# main.net
KiCad netlist of a schematic drawn in EAGLE
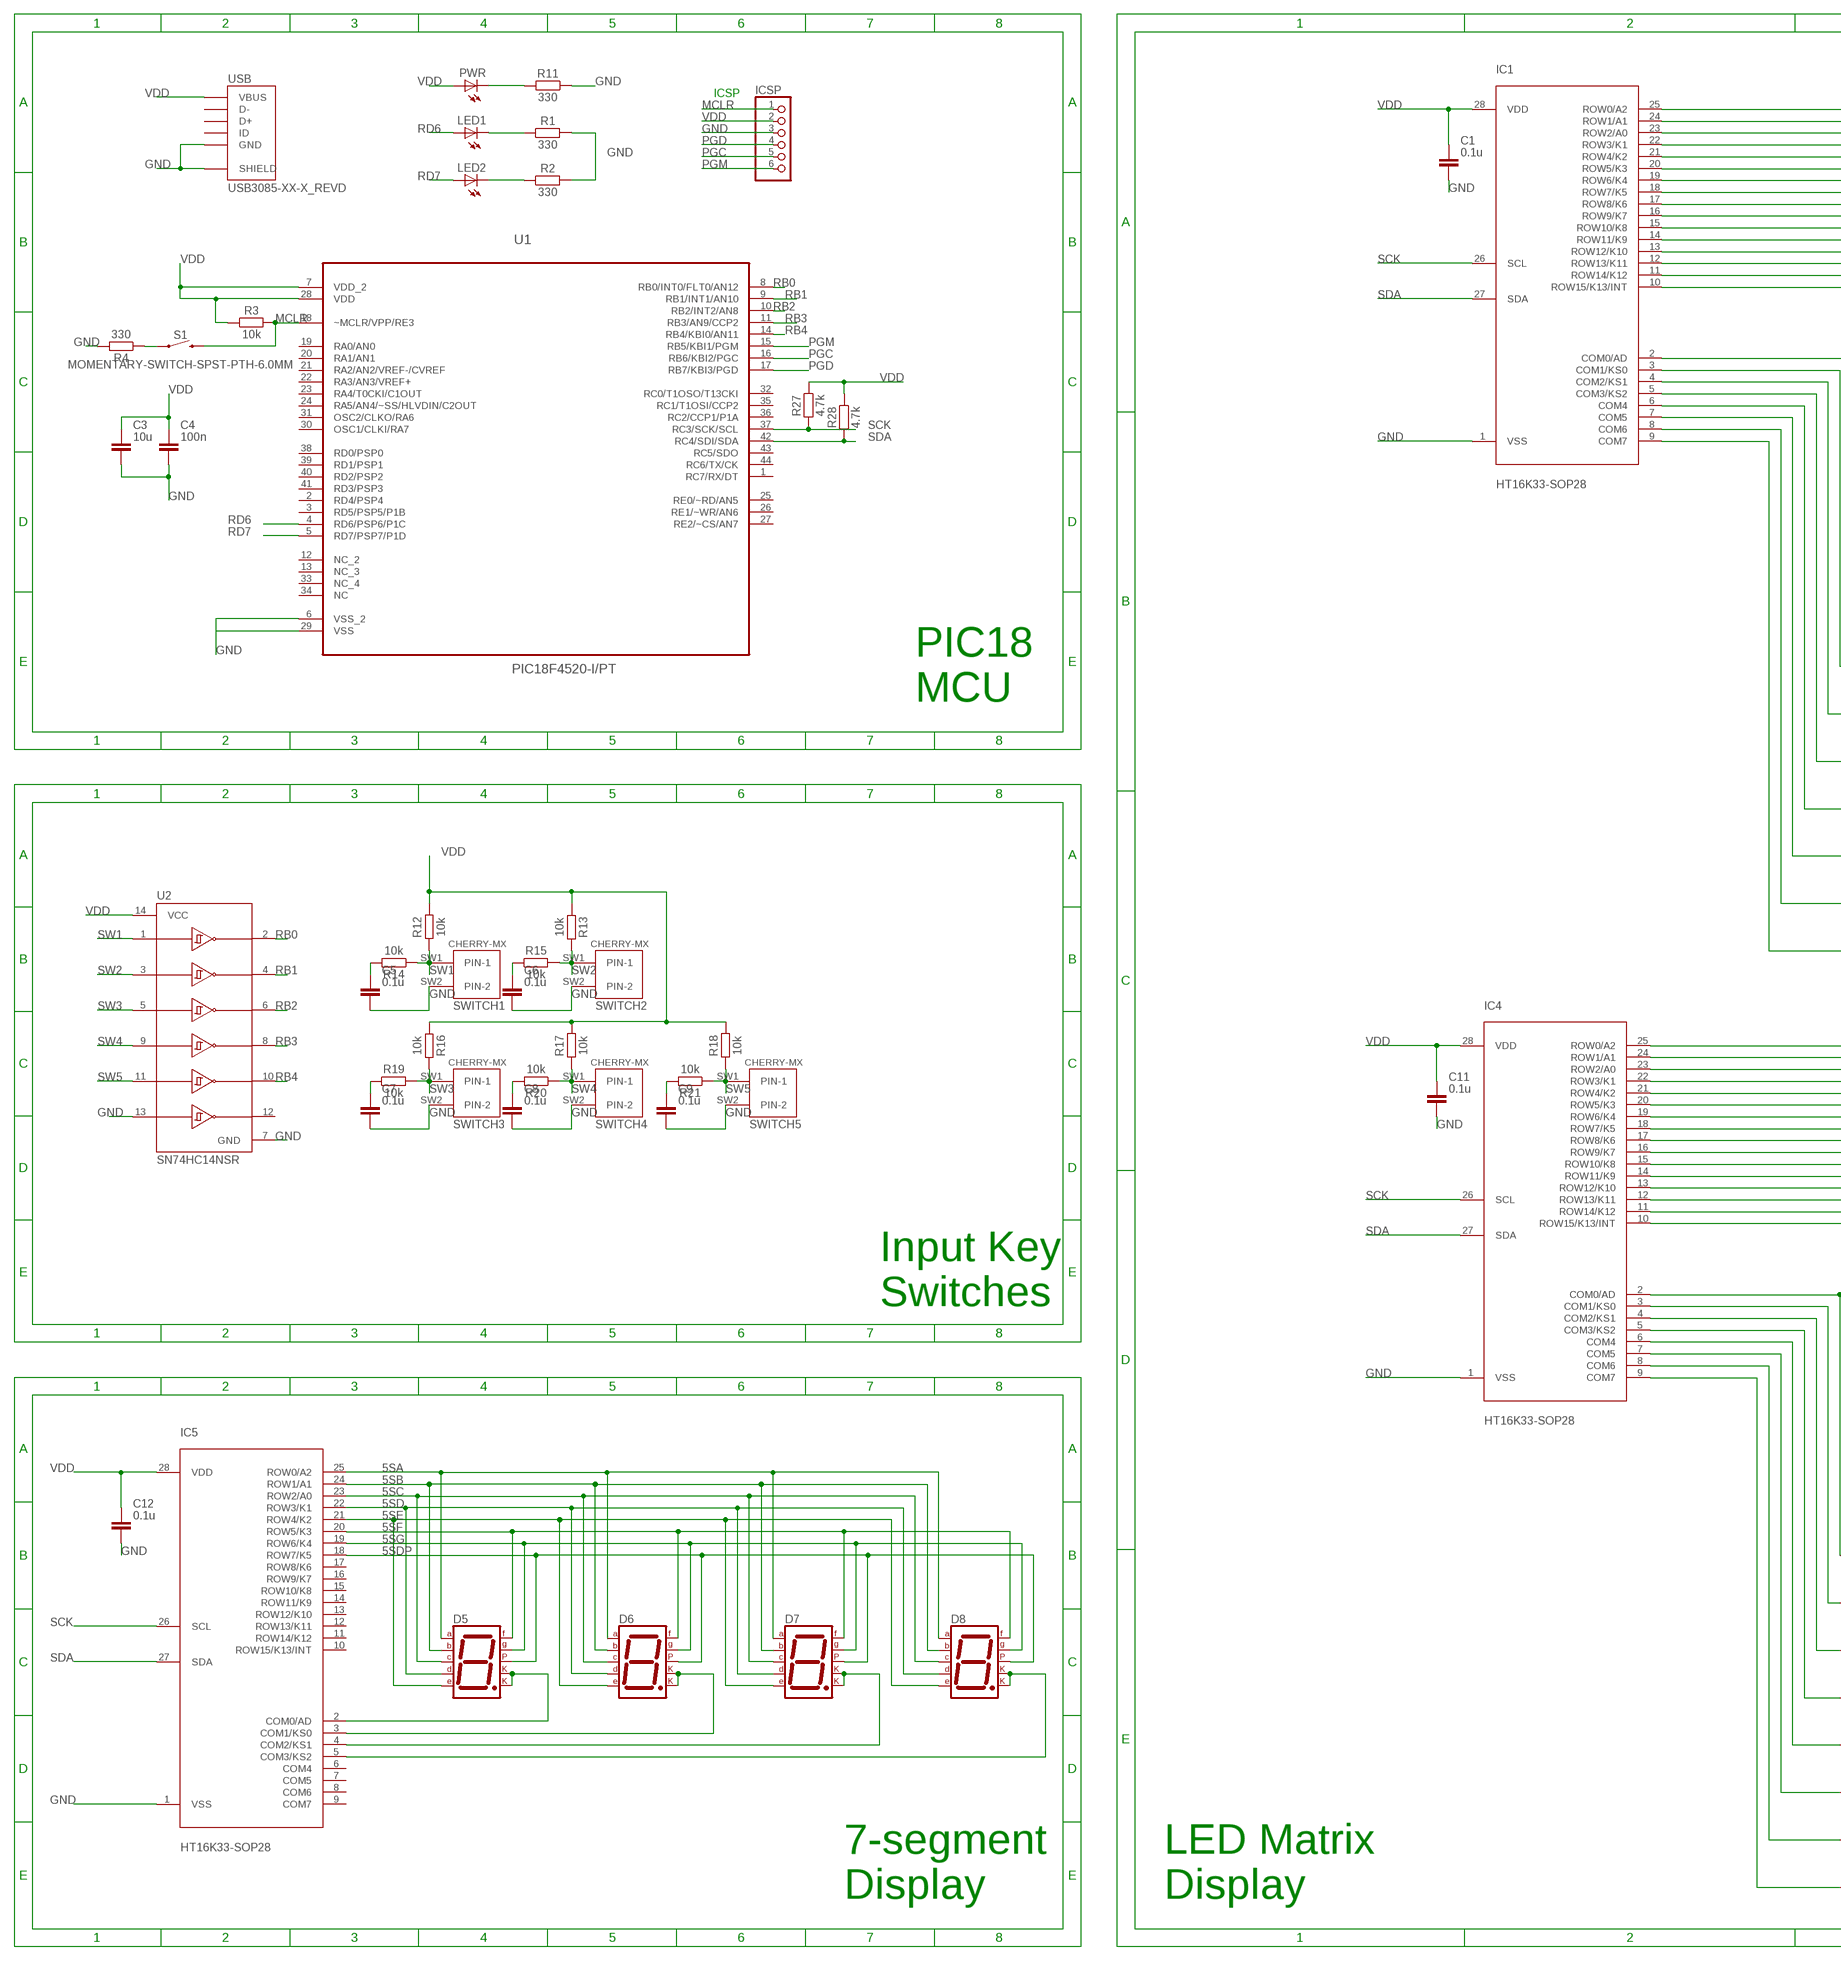
[diagram p0: schematic, sheet 1, part 1 of 2]
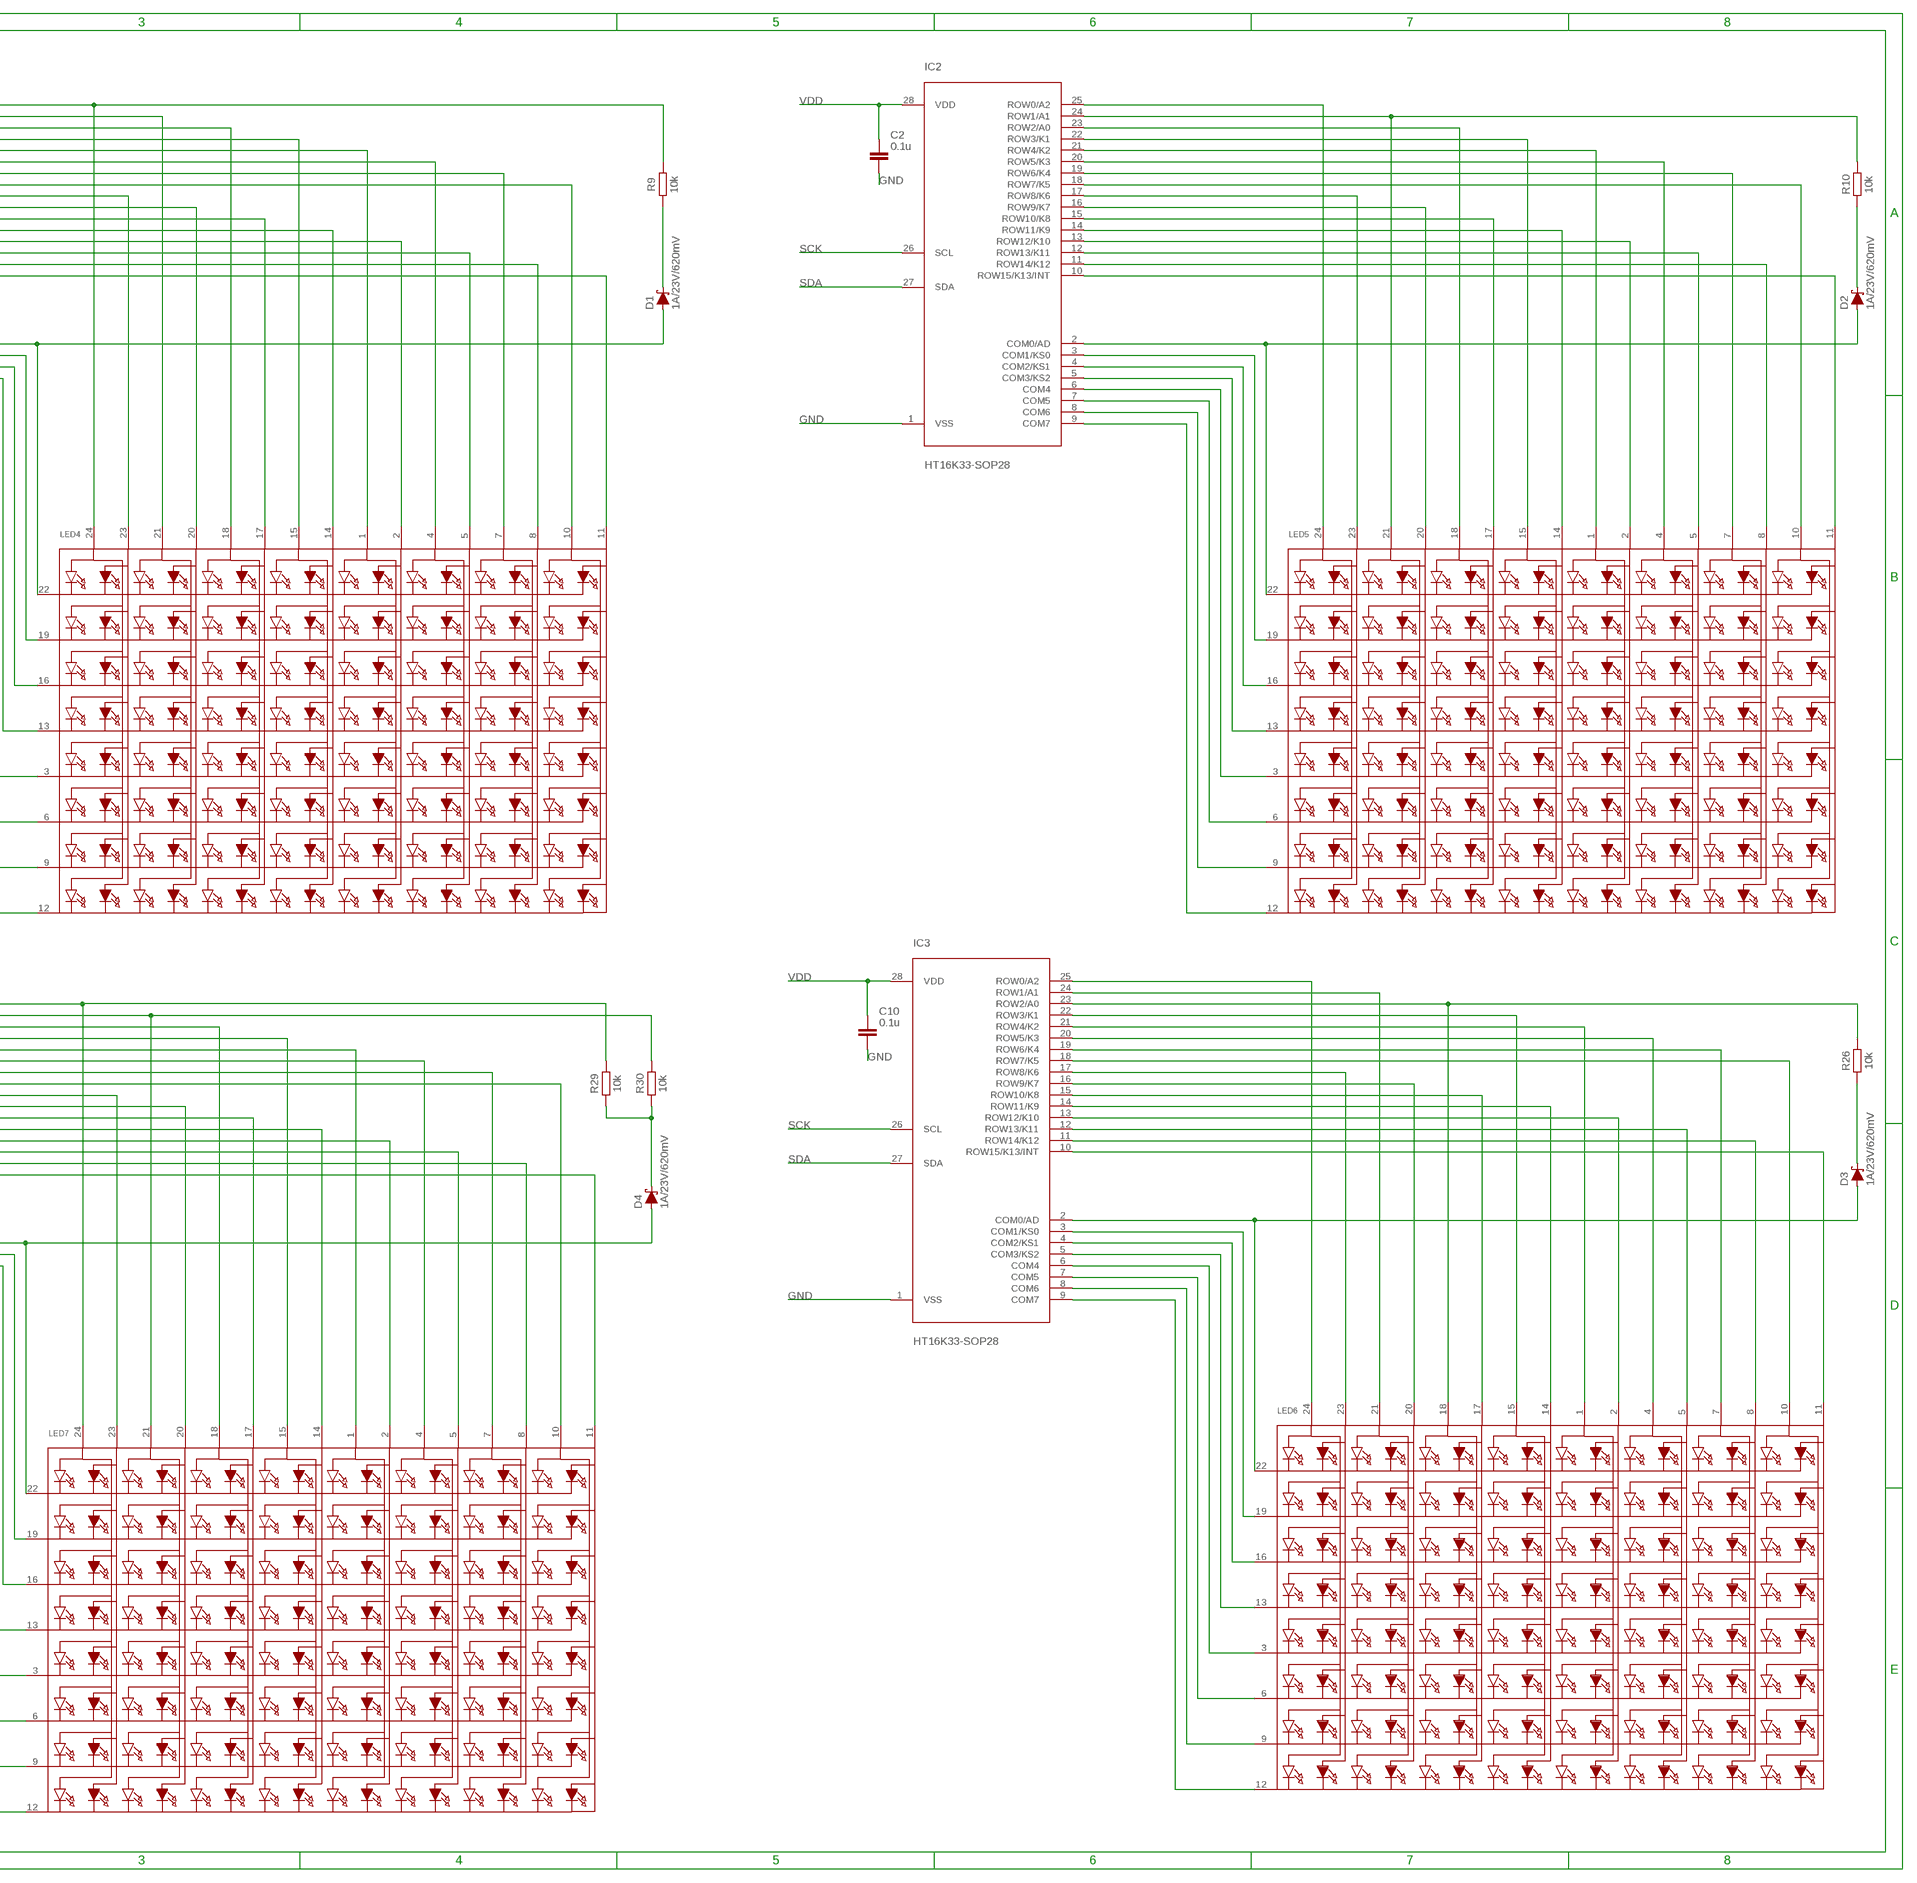
[diagram p1: schematic, sheet 1, part 2 of 2]

(export (version "E")
  (design (tool "Eeschema 10.0.6"))
  (components
    (comp (ref "C1")
      (value "0.1u")
      (footprint "eagle-import:CAPC2012X110")
      (libsource (lib "eagle-import") (part "CCHIP-0805(2012-METRIC)_"))
    )
    (comp (ref "C2")
      (value "0.1u")
      (footprint "eagle-import:CAPC2012X110")
      (libsource (lib "eagle-import") (part "CCHIP-0805(2012-METRIC)_"))
    )
    (comp (ref "C3")
      (value "10u")
      (footprint "eagle-import:CAPC2012X110")
      (libsource (lib "eagle-import") (part "CCHIP-0805(2012-METRIC)_"))
    )
    (comp (ref "C4")
      (value "100n")
      (footprint "eagle-import:CAPC2012X110")
      (libsource (lib "eagle-import") (part "CCHIP-0805(2012-METRIC)_"))
    )
    (comp (ref "C5")
      (value "0.1u")
      (footprint "eagle-import:CAPC2012X110")
      (libsource (lib "eagle-import") (part "CCHIP-0805(2012-METRIC)_"))
    )
    (comp (ref "C6")
      (value "0.1u")
      (footprint "eagle-import:CAPC2012X110")
      (libsource (lib "eagle-import") (part "CCHIP-0805(2012-METRIC)_"))
    )
    (comp (ref "C7")
      (value "0.1u")
      (footprint "eagle-import:CAPC2012X110")
      (libsource (lib "eagle-import") (part "CCHIP-0805(2012-METRIC)_"))
    )
    (comp (ref "C8")
      (value "0.1u")
      (footprint "eagle-import:CAPC2012X110")
      (libsource (lib "eagle-import") (part "CCHIP-0805(2012-METRIC)_"))
    )
    (comp (ref "C9")
      (value "0.1u")
      (footprint "eagle-import:CAPC2012X110")
      (libsource (lib "eagle-import") (part "CCHIP-0805(2012-METRIC)_"))
    )
    (comp (ref "C10")
      (value "0.1u")
      (footprint "eagle-import:CAPC2012X110")
      (libsource (lib "eagle-import") (part "CCHIP-0805(2012-METRIC)_"))
    )
    (comp (ref "C11")
      (value "0.1u")
      (footprint "eagle-import:CAPC2012X110")
      (libsource (lib "eagle-import") (part "CCHIP-0805(2012-METRIC)_"))
    )
    (comp (ref "C12")
      (value "0.1u")
      (footprint "eagle-import:CAPC2012X110")
      (libsource (lib "eagle-import") (part "CCHIP-0805(2012-METRIC)_"))
    )
    (comp (ref "D1")
      (value "1A/23V/620mV")
      (footprint "eagle-import:SOD-323")
      (libsource (lib "eagle-import") (part "DIODE-SCHOTTKY-BAT20J"))
    )
    (comp (ref "D2")
      (value "1A/23V/620mV")
      (footprint "eagle-import:SOD-323")
      (libsource (lib "eagle-import") (part "DIODE-SCHOTTKY-BAT20J"))
    )
    (comp (ref "D3")
      (value "1A/23V/620mV")
      (footprint "eagle-import:SOD-323")
      (libsource (lib "eagle-import") (part "DIODE-SCHOTTKY-BAT20J"))
    )
    (comp (ref "D4")
      (value "1A/23V/620mV")
      (footprint "eagle-import:SOD-323")
      (libsource (lib "eagle-import") (part "DIODE-SCHOTTKY-BAT20J"))
    )
    (comp (ref "D5")
      (value "7SEG-CK")
      (footprint "eagle-import:7SEG-13")
      (libsource (lib "eagle-import") (part "7SEG-CK"))
    )
    (comp (ref "D6")
      (value "7SEG-CK")
      (footprint "eagle-import:7SEG-13")
      (libsource (lib "eagle-import") (part "7SEG-CK"))
    )
    (comp (ref "D7")
      (value "7SEG-CK")
      (footprint "eagle-import:7SEG-13")
      (libsource (lib "eagle-import") (part "7SEG-CK"))
    )
    (comp (ref "D8")
      (value "7SEG-CK")
      (footprint "eagle-import:7SEG-13")
      (libsource (lib "eagle-import") (part "7SEG-CK"))
    )
    (comp (ref "IC1")
      (value "HT16K33-SOP28")
      (footprint "eagle-import:SOIC127P1031X264-28N")
      (libsource (lib "eagle-import") (part "HT16K33-SOP28"))
    )
    (comp (ref "IC2")
      (value "HT16K33-SOP28")
      (footprint "eagle-import:SOIC127P1031X264-28N")
      (libsource (lib "eagle-import") (part "HT16K33-SOP28"))
    )
    (comp (ref "IC3")
      (value "HT16K33-SOP28")
      (footprint "eagle-import:SOIC127P1031X264-28N")
      (libsource (lib "eagle-import") (part "HT16K33-SOP28"))
    )
    (comp (ref "IC4")
      (value "HT16K33-SOP28")
      (footprint "eagle-import:SOIC127P1031X264-28N")
      (libsource (lib "eagle-import") (part "HT16K33-SOP28"))
    )
    (comp (ref "IC5")
      (value "HT16K33-SOP28")
      (footprint "eagle-import:SOIC127P1031X264-28N")
      (libsource (lib "eagle-import") (part "HT16K33-SOP28"))
    )
    (comp (ref "ICSP")
      (value "PINHD-1X6")
      (footprint "eagle-import:1X06")
      (libsource (lib "eagle-import") (part "PINHD-1X6"))
    )
    (comp (ref "LED1")
      (value "LEDCHIPLED_0805")
      (footprint "eagle-import:CHIPLED_0805")
      (libsource (lib "eagle-import") (part "LEDCHIPLED_0805"))
    )
    (comp (ref "LED2")
      (value "LEDCHIPLED_0805")
      (footprint "eagle-import:CHIPLED_0805")
      (libsource (lib "eagle-import") (part "LEDCHIPLED_0805"))
    )
    (comp (ref "LED4")
      (value "SEGMENT_8X8_BICOLOR_ROWCATHODEMI2A883XX")
      (footprint "eagle-import:SEGMENT_BICOL_BL-M12A883XX")
      (libsource (lib "eagle-import") (part "SEGMENT_8X8_BICOLOR_ROWCATHODEMI2A883XX"))
    )
    (comp (ref "LED5")
      (value "SEGMENT_8X8_BICOLOR_ROWCATHODEMI2A883XX")
      (footprint "eagle-import:SEGMENT_BICOL_BL-M12A883XX")
      (libsource (lib "eagle-import") (part "SEGMENT_8X8_BICOLOR_ROWCATHODEMI2A883XX"))
    )
    (comp (ref "LED6")
      (value "SEGMENT_8X8_BICOLOR_ROWCATHODEMI2A883XX")
      (footprint "eagle-import:SEGMENT_BICOL_BL-M12A883XX")
      (libsource (lib "eagle-import") (part "SEGMENT_8X8_BICOLOR_ROWCATHODEMI2A883XX"))
    )
    (comp (ref "LED7")
      (value "SEGMENT_8X8_BICOLOR_ROWCATHODEMI2A883XX")
      (footprint "eagle-import:SEGMENT_BICOL_BL-M12A883XX")
      (libsource (lib "eagle-import") (part "SEGMENT_8X8_BICOLOR_ROWCATHODEMI2A883XX"))
    )
    (comp (ref "PWR")
      (value "LEDCHIPLED_0805")
      (footprint "eagle-import:CHIPLED_0805")
      (libsource (lib "eagle-import") (part "LEDCHIPLED_0805"))
    )
    (comp (ref "R1")
      (value "330")
      (footprint "eagle-import:RESC2012X65")
      (libsource (lib "eagle-import") (part "RCHIP-0805(2012-METRIC)_"))
    )
    (comp (ref "R2")
      (value "330")
      (footprint "eagle-import:RESC2012X65")
      (libsource (lib "eagle-import") (part "RCHIP-0805(2012-METRIC)_"))
    )
    (comp (ref "R3")
      (value "10k")
      (footprint "eagle-import:RESC2012X65")
      (libsource (lib "eagle-import") (part "RCHIP-0805(2012-METRIC)_"))
    )
    (comp (ref "R4")
      (value "330")
      (footprint "eagle-import:RESC2012X65")
      (libsource (lib "eagle-import") (part "RCHIP-0805(2012-METRIC)_"))
    )
    (comp (ref "R9")
      (value "10k")
      (footprint "eagle-import:RESC2012X65")
      (libsource (lib "eagle-import") (part "RCHIP-0805(2012-METRIC)_"))
    )
    (comp (ref "R10")
      (value "10k")
      (footprint "eagle-import:RESC2012X65")
      (libsource (lib "eagle-import") (part "RCHIP-0805(2012-METRIC)_"))
    )
    (comp (ref "R11")
      (value "330")
      (footprint "eagle-import:RESC2012X65")
      (libsource (lib "eagle-import") (part "RCHIP-0805(2012-METRIC)_"))
    )
    (comp (ref "R12")
      (value "10k")
      (footprint "eagle-import:RESC2012X65")
      (libsource (lib "eagle-import") (part "RCHIP-0805(2012-METRIC)_"))
    )
    (comp (ref "R13")
      (value "10k")
      (footprint "eagle-import:RESC2012X65")
      (libsource (lib "eagle-import") (part "RCHIP-0805(2012-METRIC)_"))
    )
    (comp (ref "R14")
      (value "10k")
      (footprint "eagle-import:RESC2012X65")
      (libsource (lib "eagle-import") (part "RCHIP-0805(2012-METRIC)_"))
    )
    (comp (ref "R15")
      (value "10k")
      (footprint "eagle-import:RESC2012X65")
      (libsource (lib "eagle-import") (part "RCHIP-0805(2012-METRIC)_"))
    )
    (comp (ref "R16")
      (value "10k")
      (footprint "eagle-import:RESC2012X65")
      (libsource (lib "eagle-import") (part "RCHIP-0805(2012-METRIC)_"))
    )
    (comp (ref "R17")
      (value "10k")
      (footprint "eagle-import:RESC2012X65")
      (libsource (lib "eagle-import") (part "RCHIP-0805(2012-METRIC)_"))
    )
    (comp (ref "R18")
      (value "10k")
      (footprint "eagle-import:RESC2012X65")
      (libsource (lib "eagle-import") (part "RCHIP-0805(2012-METRIC)_"))
    )
    (comp (ref "R19")
      (value "10k")
      (footprint "eagle-import:RESC2012X65")
      (libsource (lib "eagle-import") (part "RCHIP-0805(2012-METRIC)_"))
    )
    (comp (ref "R20")
      (value "10k")
      (footprint "eagle-import:RESC2012X65")
      (libsource (lib "eagle-import") (part "RCHIP-0805(2012-METRIC)_"))
    )
    (comp (ref "R21")
      (value "10k")
      (footprint "eagle-import:RESC2012X65")
      (libsource (lib "eagle-import") (part "RCHIP-0805(2012-METRIC)_"))
    )
    (comp (ref "R26")
      (value "10k")
      (footprint "eagle-import:RESC2012X65")
      (libsource (lib "eagle-import") (part "RCHIP-0805(2012-METRIC)_"))
    )
    (comp (ref "R27")
      (value "4.7k")
      (footprint "eagle-import:RESC2012X65")
      (libsource (lib "eagle-import") (part "RCHIP-0805(2012-METRIC)_"))
    )
    (comp (ref "R28")
      (value "4.7k")
      (footprint "eagle-import:RESC2012X65")
      (libsource (lib "eagle-import") (part "RCHIP-0805(2012-METRIC)_"))
    )
    (comp (ref "R29")
      (value "10k")
      (footprint "eagle-import:RESC2012X65")
      (libsource (lib "eagle-import") (part "RCHIP-0805(2012-METRIC)_"))
    )
    (comp (ref "R30")
      (value "10k")
      (footprint "eagle-import:RESC2012X65")
      (libsource (lib "eagle-import") (part "RCHIP-0805(2012-METRIC)_"))
    )
    (comp (ref "S1")
      (value "MOMENTARY-SWITCH-SPST-PTH-6.0MM")
      (footprint "eagle-import:TACTILE_SWITCH_PTH_6.0MM")
      (libsource (lib "eagle-import") (part "MOMENTARY-SWITCH-SPST-PTH-6.0MM"))
    )
    (comp (ref "SWITCH1")
      (value "CHERRY-MX")
      (footprint "eagle-import:CHERRY-MX")
      (libsource (lib "eagle-import") (part "CHERRY-MX"))
    )
    (comp (ref "SWITCH2")
      (value "CHERRY-MX")
      (footprint "eagle-import:CHERRY-MX")
      (libsource (lib "eagle-import") (part "CHERRY-MX"))
    )
    (comp (ref "SWITCH3")
      (value "CHERRY-MX")
      (footprint "eagle-import:CHERRY-MX")
      (libsource (lib "eagle-import") (part "CHERRY-MX"))
    )
    (comp (ref "SWITCH4")
      (value "CHERRY-MX")
      (footprint "eagle-import:CHERRY-MX")
      (libsource (lib "eagle-import") (part "CHERRY-MX"))
    )
    (comp (ref "SWITCH5")
      (value "CHERRY-MX")
      (footprint "eagle-import:CHERRY-MX")
      (libsource (lib "eagle-import") (part "CHERRY-MX"))
    )
    (comp (ref "U1")
      (value "PIC18F4520-I/PT")
      (footprint "eagle-import:QFP80P1200X1200X120-44N")
      (fields (field (name "MF") "Microchip"))
      (libsource (lib "eagle-import") (part "PIC18F4520-I/PT"))
    )
    (comp (ref "U2")
      (value "SN74HC14NSR")
      (footprint "eagle-import:SOP127P780X200-14N")
      (fields (field (name "MF") "Texas Instruments"))
      (libsource (lib "eagle-import") (part "SN74HC14NSR"))
    )
    (comp (ref "USB")
      (value "USB3085-XX-X_REVD")
      (footprint "eagle-import:GCT_USB3085-XX-X_REVD")
      (fields (field (name "MF") "Global Connector Technology") (field (name "MP") "USB3085-30-A"))
      (libsource (lib "eagle-import") (part "USB3085-XX-X_REVD"))
    )
  )
  (nets
    (net (code "1") (name "/5SA") (class "Default")
      (node (ref "D5") (pin "7") (pinfunction "A_7") (pintype "passive"))
      (node (ref "D6") (pin "7") (pinfunction "A_7") (pintype "passive"))
      (node (ref "D7") (pin "7") (pinfunction "A_7") (pintype "passive"))
      (node (ref "D8") (pin "7") (pinfunction "A_7") (pintype "passive"))
      (node (ref "IC5") (pin "25") (pinfunction "ROW0/A2_25") (pintype "bidirectional"))
    )
    (net (code "2") (name "/5SB") (class "Default")
      (node (ref "D5") (pin "6") (pinfunction "B_6") (pintype "passive"))
      (node (ref "D6") (pin "6") (pinfunction "B_6") (pintype "passive"))
      (node (ref "D7") (pin "6") (pinfunction "B_6") (pintype "passive"))
      (node (ref "D8") (pin "6") (pinfunction "B_6") (pintype "passive"))
      (node (ref "IC5") (pin "24") (pinfunction "ROW1/A1_24") (pintype "bidirectional"))
    )
    (net (code "3") (name "/5SC") (class "Default")
      (node (ref "D5") (pin "4") (pinfunction "C_4") (pintype "passive"))
      (node (ref "D6") (pin "4") (pinfunction "C_4") (pintype "passive"))
      (node (ref "D7") (pin "4") (pinfunction "C_4") (pintype "passive"))
      (node (ref "D8") (pin "4") (pinfunction "C_4") (pintype "passive"))
      (node (ref "IC5") (pin "23") (pinfunction "ROW2/A0_23") (pintype "bidirectional"))
    )
    (net (code "4") (name "/5SD") (class "Default")
      (node (ref "D5") (pin "2") (pinfunction "D_2") (pintype "passive"))
      (node (ref "D6") (pin "2") (pinfunction "D_2") (pintype "passive"))
      (node (ref "D7") (pin "2") (pinfunction "D_2") (pintype "passive"))
      (node (ref "D8") (pin "2") (pinfunction "D_2") (pintype "passive"))
      (node (ref "IC5") (pin "22") (pinfunction "ROW3/K1_22") (pintype "bidirectional"))
    )
    (net (code "5") (name "/5SDP") (class "Default")
      (node (ref "D5") (pin "5") (pinfunction "DP_5") (pintype "passive"))
      (node (ref "D6") (pin "5") (pinfunction "DP_5") (pintype "passive"))
      (node (ref "D7") (pin "5") (pinfunction "DP_5") (pintype "passive"))
      (node (ref "D8") (pin "5") (pinfunction "DP_5") (pintype "passive"))
      (node (ref "IC5") (pin "18") (pinfunction "ROW7/K5_18") (pintype "bidirectional"))
    )
    (net (code "6") (name "/5SE") (class "Default")
      (node (ref "D5") (pin "1") (pinfunction "E_1") (pintype "passive"))
      (node (ref "D6") (pin "1") (pinfunction "E_1") (pintype "passive"))
      (node (ref "D7") (pin "1") (pinfunction "E_1") (pintype "passive"))
      (node (ref "D8") (pin "1") (pinfunction "E_1") (pintype "passive"))
      (node (ref "IC5") (pin "21") (pinfunction "ROW4/K2_21") (pintype "bidirectional"))
    )
    (net (code "7") (name "/5SF") (class "Default")
      (node (ref "D5") (pin "9") (pinfunction "F_9") (pintype "passive"))
      (node (ref "D6") (pin "9") (pinfunction "F_9") (pintype "passive"))
      (node (ref "D7") (pin "9") (pinfunction "F_9") (pintype "passive"))
      (node (ref "D8") (pin "9") (pinfunction "F_9") (pintype "passive"))
      (node (ref "IC5") (pin "20") (pinfunction "ROW5/K3_20") (pintype "bidirectional"))
    )
    (net (code "8") (name "/5SG") (class "Default")
      (node (ref "D5") (pin "10") (pinfunction "G_10") (pintype "passive"))
      (node (ref "D6") (pin "10") (pinfunction "G_10") (pintype "passive"))
      (node (ref "D7") (pin "10") (pinfunction "G_10") (pintype "passive"))
      (node (ref "D8") (pin "10") (pinfunction "G_10") (pintype "passive"))
      (node (ref "IC5") (pin "19") (pinfunction "ROW6/K4_19") (pintype "bidirectional"))
    )
    (net (code "9") (name "/GND") (class "Default")
      (node (ref "C1") (pin "2") (pinfunction "2_2") (pintype "passive"))
      (node (ref "C10") (pin "2") (pinfunction "2_2") (pintype "passive"))
      (node (ref "C11") (pin "2") (pinfunction "2_2") (pintype "passive"))
      (node (ref "C12") (pin "2") (pinfunction "2_2") (pintype "passive"))
      (node (ref "C2") (pin "2") (pinfunction "2_2") (pintype "passive"))
      (node (ref "C3") (pin "2") (pinfunction "2_2") (pintype "passive"))
      (node (ref "C4") (pin "2") (pinfunction "2_2") (pintype "passive"))
      (node (ref "C5") (pin "2") (pinfunction "2_2") (pintype "passive"))
      (node (ref "C6") (pin "2") (pinfunction "2_2") (pintype "passive"))
      (node (ref "C7") (pin "2") (pinfunction "2_2") (pintype "passive"))
      (node (ref "C8") (pin "2") (pinfunction "2_2") (pintype "passive"))
      (node (ref "C9") (pin "2") (pinfunction "2_2") (pintype "passive"))
      (node (ref "IC1") (pin "1") (pinfunction "VSS_1") (pintype "power_in"))
      (node (ref "IC2") (pin "1") (pinfunction "VSS_1") (pintype "power_in"))
      (node (ref "IC3") (pin "1") (pinfunction "VSS_1") (pintype "power_in"))
      (node (ref "IC4") (pin "1") (pinfunction "VSS_1") (pintype "power_in"))
      (node (ref "IC5") (pin "1") (pinfunction "VSS_1") (pintype "power_in"))
      (node (ref "ICSP") (pin "3") (pinfunction "3_3") (pintype "passive"))
      (node (ref "R1") (pin "2") (pinfunction "2_2") (pintype "passive"))
      (node (ref "R11") (pin "1") (pinfunction "1_1") (pintype "passive"))
      (node (ref "R2") (pin "2") (pinfunction "2_2") (pintype "passive"))
      (node (ref "R4") (pin "2") (pinfunction "2_2") (pintype "passive"))
      (node (ref "SWITCH1") (pin "SW2") (pinfunction "PIN-2_SW2") (pintype "bidirectional"))
      (node (ref "SWITCH2") (pin "SW2") (pinfunction "PIN-2_SW2") (pintype "bidirectional"))
      (node (ref "SWITCH3") (pin "SW2") (pinfunction "PIN-2_SW2") (pintype "bidirectional"))
      (node (ref "SWITCH4") (pin "SW2") (pinfunction "PIN-2_SW2") (pintype "bidirectional"))
      (node (ref "SWITCH5") (pin "SW2") (pinfunction "PIN-2_SW2") (pintype "bidirectional"))
      (node (ref "U1") (pin "29") (pinfunction "VSS_29") (pintype "power_in"))
      (node (ref "U1") (pin "6") (pinfunction "VSS_2_6") (pintype "power_in"))
      (node (ref "U2") (pin "13") (pinfunction "6A_13") (pintype "input"))
      (node (ref "U2") (pin "7") (pinfunction "GND_7") (pintype "power_in"))
      (node (ref "USB") (pin "5") (pinfunction "GND_5") (pintype "power_in"))
      (node (ref "USB") (pin "6") (pinfunction "SHIELD_6") (pintype "power_in"))
      (node (ref "USB") (pin "7") (pinfunction "SHIELD_7") (pintype "power_in"))
      (node (ref "USB") (pin "8") (pinfunction "SHIELD_8") (pintype "power_in"))
      (node (ref "USB") (pin "9") (pinfunction "SHIELD_9") (pintype "power_in"))
    )
    (net (code "10") (name "/MCLR") (class "Default")
      (node (ref "ICSP") (pin "1") (pinfunction "1_1") (pintype "passive"))
      (node (ref "R3") (pin "2") (pinfunction "2_2") (pintype "passive"))
      (node (ref "S1") (pin "3") (pinfunction "2_3") (pintype "passive"))
      (node (ref "U1") (pin "18") (pinfunction "~{MCLR/VPP/RE3}_18") (pintype "input"))
    )
    (net (code "11") (name "/PGC") (class "Default")
      (node (ref "ICSP") (pin "5") (pinfunction "5_5") (pintype "passive"))
      (node (ref "U1") (pin "16") (pinfunction "RB6/KBI2/PGC_16") (pintype "bidirectional"))
    )
    (net (code "12") (name "/PGD") (class "Default")
      (node (ref "ICSP") (pin "4") (pinfunction "4_4") (pintype "passive"))
      (node (ref "U1") (pin "17") (pinfunction "RB7/KBI3/PGD_17") (pintype "bidirectional"))
    )
    (net (code "13") (name "/PGM") (class "Default")
      (node (ref "ICSP") (pin "6") (pinfunction "6_6") (pintype "passive"))
      (node (ref "U1") (pin "15") (pinfunction "RB5/KBI1/PGM_15") (pintype "bidirectional"))
    )
    (net (code "14") (name "/RB0") (class "Default")
      (node (ref "U1") (pin "8") (pinfunction "RB0/INT0/FLT0/AN12_8") (pintype "bidirectional"))
      (node (ref "U2") (pin "2") (pinfunction "1Y_2") (pintype "output"))
    )
    (net (code "15") (name "/RB1") (class "Default")
      (node (ref "U1") (pin "9") (pinfunction "RB1/INT1/AN10_9") (pintype "bidirectional"))
      (node (ref "U2") (pin "4") (pinfunction "2Y_4") (pintype "output"))
    )
    (net (code "16") (name "/RB2") (class "Default")
      (node (ref "U1") (pin "10") (pinfunction "RB2/INT2/AN8_10") (pintype "bidirectional"))
      (node (ref "U2") (pin "6") (pinfunction "3Y_6") (pintype "output"))
    )
    (net (code "17") (name "/RB3") (class "Default")
      (node (ref "U1") (pin "11") (pinfunction "RB3/AN9/CCP2_11") (pintype "bidirectional"))
      (node (ref "U2") (pin "8") (pinfunction "4Y_8") (pintype "output"))
    )
    (net (code "18") (name "/RB4") (class "Default")
      (node (ref "U1") (pin "14") (pinfunction "RB4/KBI0/AN11_14") (pintype "bidirectional"))
      (node (ref "U2") (pin "10") (pinfunction "5Y_10") (pintype "output"))
    )
    (net (code "19") (name "/RD6") (class "Default")
      (node (ref "LED1") (pin "A") (pinfunction "A_A") (pintype "passive"))
      (node (ref "U1") (pin "4") (pinfunction "RD6/PSP6/P1C_4") (pintype "bidirectional"))
    )
    (net (code "20") (name "/RD7") (class "Default")
      (node (ref "LED2") (pin "A") (pinfunction "A_A") (pintype "passive"))
      (node (ref "U1") (pin "5") (pinfunction "RD7/PSP7/P1D_5") (pintype "bidirectional"))
    )
    (net (code "21") (name "/SCK") (class "Default")
      (node (ref "IC1") (pin "26") (pinfunction "SCL_26") (pintype "input"))
      (node (ref "IC2") (pin "26") (pinfunction "SCL_26") (pintype "input"))
      (node (ref "IC3") (pin "26") (pinfunction "SCL_26") (pintype "input"))
      (node (ref "IC4") (pin "26") (pinfunction "SCL_26") (pintype "input"))
      (node (ref "IC5") (pin "26") (pinfunction "SCL_26") (pintype "input"))
      (node (ref "R27") (pin "2") (pinfunction "2_2") (pintype "passive"))
      (node (ref "U1") (pin "37") (pinfunction "RC3/SCK/SCL_37") (pintype "bidirectional"))
    )
    (net (code "22") (name "/SDA") (class "Default")
      (node (ref "IC1") (pin "27") (pinfunction "SDA_27") (pintype "bidirectional"))
      (node (ref "IC2") (pin "27") (pinfunction "SDA_27") (pintype "bidirectional"))
      (node (ref "IC3") (pin "27") (pinfunction "SDA_27") (pintype "bidirectional"))
      (node (ref "IC4") (pin "27") (pinfunction "SDA_27") (pintype "bidirectional"))
      (node (ref "IC5") (pin "27") (pinfunction "SDA_27") (pintype "bidirectional"))
      (node (ref "R28") (pin "2") (pinfunction "2_2") (pintype "passive"))
      (node (ref "U1") (pin "42") (pinfunction "RC4/SDI/SDA_42") (pintype "bidirectional"))
    )
    (net (code "23") (name "/SW1") (class "Default")
      (node (ref "R12") (pin "1") (pinfunction "1_1") (pintype "passive"))
      (node (ref "R14") (pin "1") (pinfunction "1_1") (pintype "passive"))
      (node (ref "SWITCH1") (pin "SW1") (pinfunction "PIN-1_SW1") (pintype "bidirectional"))
      (node (ref "U2") (pin "1") (pinfunction "1A_1") (pintype "input"))
    )
    (net (code "24") (name "/SW2") (class "Default")
      (node (ref "R13") (pin "2") (pinfunction "2_2") (pintype "passive"))
      (node (ref "R15") (pin "2") (pinfunction "2_2") (pintype "passive"))
      (node (ref "SWITCH2") (pin "SW1") (pinfunction "PIN-1_SW1") (pintype "bidirectional"))
      (node (ref "U2") (pin "3") (pinfunction "2A_3") (pintype "input"))
    )
    (net (code "25") (name "/SW3") (class "Default")
      (node (ref "R16") (pin "2") (pinfunction "2_2") (pintype "passive"))
      (node (ref "R19") (pin "2") (pinfunction "2_2") (pintype "passive"))
      (node (ref "SWITCH3") (pin "SW1") (pinfunction "PIN-1_SW1") (pintype "bidirectional"))
      (node (ref "U2") (pin "5") (pinfunction "3A_5") (pintype "input"))
    )
    (net (code "26") (name "/SW4") (class "Default")
      (node (ref "R17") (pin "1") (pinfunction "1_1") (pintype "passive"))
      (node (ref "R20") (pin "1") (pinfunction "1_1") (pintype "passive"))
      (node (ref "SWITCH4") (pin "SW1") (pinfunction "PIN-1_SW1") (pintype "bidirectional"))
      (node (ref "U2") (pin "9") (pinfunction "4A_9") (pintype "input"))
    )
    (net (code "27") (name "/SW5") (class "Default")
      (node (ref "R18") (pin "1") (pinfunction "1_1") (pintype "passive"))
      (node (ref "R21") (pin "1") (pinfunction "1_1") (pintype "passive"))
      (node (ref "SWITCH5") (pin "SW1") (pinfunction "PIN-1_SW1") (pintype "bidirectional"))
      (node (ref "U2") (pin "11") (pinfunction "5A_11") (pintype "input"))
    )
    (net (code "28") (name "/VDD") (class "Default")
      (node (ref "C1") (pin "1") (pinfunction "1_1") (pintype "passive"))
      (node (ref "C10") (pin "1") (pinfunction "1_1") (pintype "passive"))
      (node (ref "C11") (pin "1") (pinfunction "1_1") (pintype "passive"))
      (node (ref "C12") (pin "1") (pinfunction "1_1") (pintype "passive"))
      (node (ref "C2") (pin "1") (pinfunction "1_1") (pintype "passive"))
      (node (ref "C3") (pin "1") (pinfunction "1_1") (pintype "passive"))
      (node (ref "C4") (pin "1") (pinfunction "1_1") (pintype "passive"))
      (node (ref "IC1") (pin "28") (pinfunction "VDD_28") (pintype "power_in"))
      (node (ref "IC2") (pin "28") (pinfunction "VDD_28") (pintype "power_in"))
      (node (ref "IC3") (pin "28") (pinfunction "VDD_28") (pintype "power_in"))
      (node (ref "IC4") (pin "28") (pinfunction "VDD_28") (pintype "power_in"))
      (node (ref "IC5") (pin "28") (pinfunction "VDD_28") (pintype "power_in"))
      (node (ref "ICSP") (pin "2") (pinfunction "2_2") (pintype "passive"))
      (node (ref "PWR") (pin "A") (pinfunction "A_A") (pintype "passive"))
      (node (ref "R12") (pin "2") (pinfunction "2_2") (pintype "passive"))
      (node (ref "R13") (pin "1") (pinfunction "1_1") (pintype "passive"))
      (node (ref "R16") (pin "1") (pinfunction "1_1") (pintype "passive"))
      (node (ref "R17") (pin "2") (pinfunction "2_2") (pintype "passive"))
      (node (ref "R18") (pin "2") (pinfunction "2_2") (pintype "passive"))
      (node (ref "R27") (pin "1") (pinfunction "1_1") (pintype "passive"))
      (node (ref "R28") (pin "1") (pinfunction "1_1") (pintype "passive"))
      (node (ref "R3") (pin "1") (pinfunction "1_1") (pintype "passive"))
      (node (ref "U1") (pin "28") (pinfunction "VDD_28") (pintype "power_in"))
      (node (ref "U1") (pin "7") (pinfunction "VDD_2_7") (pintype "power_in"))
      (node (ref "U2") (pin "14") (pinfunction "VCC_14") (pintype "power_in"))
      (node (ref "USB") (pin "1") (pinfunction "VBUS_1") (pintype "power_in"))
    )
    (net (code "29") (name "Net-(C5-Pad1)") (class "Default")
      (node (ref "C5") (pin "1") (pinfunction "1_1") (pintype "passive"))
      (node (ref "R14") (pin "2") (pinfunction "2_2") (pintype "passive"))
    )
    (net (code "30") (name "Net-(C6-Pad1)") (class "Default")
      (node (ref "C6") (pin "1") (pinfunction "1_1") (pintype "passive"))
      (node (ref "R15") (pin "1") (pinfunction "1_1") (pintype "passive"))
    )
    (net (code "31") (name "Net-(C7-Pad1)") (class "Default")
      (node (ref "C7") (pin "1") (pinfunction "1_1") (pintype "passive"))
      (node (ref "R19") (pin "1") (pinfunction "1_1") (pintype "passive"))
    )
    (net (code "32") (name "Net-(C8-Pad1)") (class "Default")
      (node (ref "C8") (pin "1") (pinfunction "1_1") (pintype "passive"))
      (node (ref "R20") (pin "2") (pinfunction "2_2") (pintype "passive"))
    )
    (net (code "33") (name "Net-(C9-Pad1)") (class "Default")
      (node (ref "C9") (pin "1") (pinfunction "1_1") (pintype "passive"))
      (node (ref "R21") (pin "2") (pinfunction "2_2") (pintype "passive"))
    )
    (net (code "34") (name "Net-(D1-PadC)") (class "Default")
      (node (ref "D1") (pin "C") (pinfunction "C_C") (pintype "passive"))
      (node (ref "R9") (pin "1") (pinfunction "1_1") (pintype "passive"))
    )
    (net (code "35") (name "Net-(D2-PadC)") (class "Default")
      (node (ref "D2") (pin "C") (pinfunction "C_C") (pintype "passive"))
      (node (ref "R10") (pin "1") (pinfunction "1_1") (pintype "passive"))
    )
    (net (code "36") (name "Net-(D3-PadC)") (class "Default")
      (node (ref "D3") (pin "C") (pinfunction "C_C") (pintype "passive"))
      (node (ref "R26") (pin "1") (pinfunction "1_1") (pintype "passive"))
    )
    (net (code "37") (name "Net-(D4-PadC)") (class "Default")
      (node (ref "D4") (pin "C") (pinfunction "C_C") (pintype "passive"))
      (node (ref "R29") (pin "1") (pinfunction "1_1") (pintype "passive"))
      (node (ref "R30") (pin "1") (pinfunction "1_1") (pintype "passive"))
    )
    (net (code "38") (name "Net-(D5-CK1)") (class "Default")
      (node (ref "D5") (pin "3") (pinfunction "CK1_3") (pintype "passive"))
      (node (ref "D5") (pin "8") (pinfunction "CK2_8") (pintype "passive"))
      (node (ref "IC5") (pin "2") (pinfunction "COM0/AD_2") (pintype "output"))
    )
    (net (code "39") (name "Net-(D6-CK1)") (class "Default")
      (node (ref "D6") (pin "3") (pinfunction "CK1_3") (pintype "passive"))
      (node (ref "D6") (pin "8") (pinfunction "CK2_8") (pintype "passive"))
      (node (ref "IC5") (pin "3") (pinfunction "COM1/KS0_3") (pintype "output"))
    )
    (net (code "40") (name "Net-(D7-CK1)") (class "Default")
      (node (ref "D7") (pin "3") (pinfunction "CK1_3") (pintype "passive"))
      (node (ref "D7") (pin "8") (pinfunction "CK2_8") (pintype "passive"))
      (node (ref "IC5") (pin "4") (pinfunction "COM2/KS1_4") (pintype "output"))
    )
    (net (code "41") (name "Net-(D8-CK1)") (class "Default")
      (node (ref "D8") (pin "3") (pinfunction "CK1_3") (pintype "passive"))
      (node (ref "D8") (pin "8") (pinfunction "CK2_8") (pintype "passive"))
      (node (ref "IC5") (pin "5") (pinfunction "COM3/KS2_5") (pintype "output"))
    )
    (net (code "42") (name "Net-(IC1-COM0{slash}AD)") (class "Default")
      (node (ref "D1") (pin "A") (pinfunction "A_A") (pintype "passive"))
      (node (ref "IC1") (pin "2") (pinfunction "COM0/AD_2") (pintype "output"))
      (node (ref "LED4") (pin "22") (pinfunction "K1_22") (pintype "bidirectional"))
    )
    (net (code "43") (name "Net-(IC1-COM1{slash}KS0)") (class "Default")
      (node (ref "IC1") (pin "3") (pinfunction "COM1/KS0_3") (pintype "output"))
      (node (ref "LED4") (pin "19") (pinfunction "K2_19") (pintype "bidirectional"))
    )
    (net (code "44") (name "Net-(IC1-COM2{slash}KS1)") (class "Default")
      (node (ref "IC1") (pin "4") (pinfunction "COM2/KS1_4") (pintype "output"))
      (node (ref "LED4") (pin "16") (pinfunction "K3_16") (pintype "bidirectional"))
    )
    (net (code "45") (name "Net-(IC1-COM3{slash}KS2)") (class "Default")
      (node (ref "IC1") (pin "5") (pinfunction "COM3/KS2_5") (pintype "output"))
      (node (ref "LED4") (pin "13") (pinfunction "K4_13") (pintype "bidirectional"))
    )
    (net (code "46") (name "Net-(IC1-COM4)") (class "Default")
      (node (ref "IC1") (pin "6") (pinfunction "COM4_6") (pintype "output"))
      (node (ref "LED4") (pin "3") (pinfunction "K5_3") (pintype "bidirectional"))
    )
    (net (code "47") (name "Net-(IC1-COM5)") (class "Default")
      (node (ref "IC1") (pin "7") (pinfunction "COM5_7") (pintype "output"))
      (node (ref "LED4") (pin "6") (pinfunction "K6_6") (pintype "bidirectional"))
    )
    (net (code "48") (name "Net-(IC1-COM6)") (class "Default")
      (node (ref "IC1") (pin "8") (pinfunction "COM6_8") (pintype "output"))
      (node (ref "LED4") (pin "9") (pinfunction "K7_9") (pintype "bidirectional"))
    )
    (net (code "49") (name "Net-(IC1-COM7)") (class "Default")
      (node (ref "IC1") (pin "9") (pinfunction "COM7_9") (pintype "output"))
      (node (ref "LED4") (pin "12") (pinfunction "K8_12") (pintype "bidirectional"))
    )
    (net (code "50") (name "Net-(IC1-ROW0{slash}A2)") (class "Default")
      (node (ref "IC1") (pin "25") (pinfunction "ROW0/A2_25") (pintype "bidirectional"))
      (node (ref "LED4") (pin "24") (pinfunction "A1_24") (pintype "bidirectional"))
      (node (ref "R9") (pin "2") (pinfunction "2_2") (pintype "passive"))
    )
    (net (code "51") (name "Net-(IC1-ROW1{slash}A1)") (class "Default")
      (node (ref "IC1") (pin "24") (pinfunction "ROW1/A1_24") (pintype "bidirectional"))
      (node (ref "LED4") (pin "21") (pinfunction "A3_21") (pintype "bidirectional"))
    )
    (net (code "52") (name "Net-(IC1-ROW2{slash}A0)") (class "Default")
      (node (ref "IC1") (pin "23") (pinfunction "ROW2/A0_23") (pintype "bidirectional"))
      (node (ref "LED4") (pin "18") (pinfunction "A5_18") (pintype "bidirectional"))
    )
    (net (code "53") (name "Net-(IC1-ROW3{slash}K1)") (class "Default")
      (node (ref "IC1") (pin "22") (pinfunction "ROW3/K1_22") (pintype "bidirectional"))
      (node (ref "LED4") (pin "15") (pinfunction "A7_15") (pintype "bidirectional"))
    )
    (net (code "54") (name "Net-(IC1-ROW4{slash}K2)") (class "Default")
      (node (ref "IC1") (pin "21") (pinfunction "ROW4/K2_21") (pintype "bidirectional"))
      (node (ref "LED4") (pin "1") (pinfunction "A9_1") (pintype "bidirectional"))
    )
    (net (code "55") (name "Net-(IC1-ROW5{slash}K3)") (class "Default")
      (node (ref "IC1") (pin "20") (pinfunction "ROW5/K3_20") (pintype "bidirectional"))
      (node (ref "LED4") (pin "4") (pinfunction "A11_4") (pintype "bidirectional"))
    )
    (net (code "56") (name "Net-(IC1-ROW6{slash}K4)") (class "Default")
      (node (ref "IC1") (pin "19") (pinfunction "ROW6/K4_19") (pintype "bidirectional"))
      (node (ref "LED4") (pin "7") (pinfunction "A13_7") (pintype "bidirectional"))
    )
    (net (code "57") (name "Net-(IC1-ROW7{slash}K5)") (class "Default")
      (node (ref "IC1") (pin "18") (pinfunction "ROW7/K5_18") (pintype "bidirectional"))
      (node (ref "LED4") (pin "10") (pinfunction "A15_10") (pintype "bidirectional"))
    )
    (net (code "58") (name "Net-(IC1-ROW8{slash}K6)") (class "Default")
      (node (ref "IC1") (pin "17") (pinfunction "ROW8/K6_17") (pintype "bidirectional"))
      (node (ref "LED4") (pin "23") (pinfunction "A2_23") (pintype "bidirectional"))
    )
    (net (code "59") (name "Net-(IC1-ROW9{slash}K7)") (class "Default")
      (node (ref "IC1") (pin "16") (pinfunction "ROW9/K7_16") (pintype "bidirectional"))
      (node (ref "LED4") (pin "20") (pinfunction "A4_20") (pintype "bidirectional"))
    )
    (net (code "60") (name "Net-(IC1-ROW10{slash}K8)") (class "Default")
      (node (ref "IC1") (pin "15") (pinfunction "ROW10/K8_15") (pintype "bidirectional"))
      (node (ref "LED4") (pin "17") (pinfunction "A6_17") (pintype "bidirectional"))
    )
    (net (code "61") (name "Net-(IC1-ROW11{slash}K9)") (class "Default")
      (node (ref "IC1") (pin "14") (pinfunction "ROW11/K9_14") (pintype "bidirectional"))
      (node (ref "LED4") (pin "14") (pinfunction "A8_14") (pintype "bidirectional"))
    )
    (net (code "62") (name "Net-(IC1-ROW12{slash}K10)") (class "Default")
      (node (ref "IC1") (pin "13") (pinfunction "ROW12/K10_13") (pintype "bidirectional"))
      (node (ref "LED4") (pin "2") (pinfunction "A10_2") (pintype "bidirectional"))
    )
    (net (code "63") (name "Net-(IC1-ROW13{slash}K11)") (class "Default")
      (node (ref "IC1") (pin "12") (pinfunction "ROW13/K11_12") (pintype "bidirectional"))
      (node (ref "LED4") (pin "5") (pinfunction "A12_5") (pintype "bidirectional"))
    )
    (net (code "64") (name "Net-(IC1-ROW14{slash}K12)") (class "Default")
      (node (ref "IC1") (pin "11") (pinfunction "ROW14/K12_11") (pintype "bidirectional"))
      (node (ref "LED4") (pin "8") (pinfunction "A14_8") (pintype "bidirectional"))
    )
    (net (code "65") (name "Net-(IC1-ROW15{slash}K13{slash}INT)") (class "Default")
      (node (ref "IC1") (pin "10") (pinfunction "ROW15/K13/INT_10") (pintype "bidirectional"))
      (node (ref "LED4") (pin "11") (pinfunction "A16_11") (pintype "bidirectional"))
    )
    (net (code "66") (name "Net-(IC2-COM0{slash}AD)") (class "Default")
      (node (ref "D2") (pin "A") (pinfunction "A_A") (pintype "passive"))
      (node (ref "IC2") (pin "2") (pinfunction "COM0/AD_2") (pintype "output"))
      (node (ref "LED5") (pin "22") (pinfunction "K1_22") (pintype "bidirectional"))
    )
    (net (code "67") (name "Net-(IC2-COM1{slash}KS0)") (class "Default")
      (node (ref "IC2") (pin "3") (pinfunction "COM1/KS0_3") (pintype "output"))
      (node (ref "LED5") (pin "19") (pinfunction "K2_19") (pintype "bidirectional"))
    )
    (net (code "68") (name "Net-(IC2-COM2{slash}KS1)") (class "Default")
      (node (ref "IC2") (pin "4") (pinfunction "COM2/KS1_4") (pintype "output"))
      (node (ref "LED5") (pin "16") (pinfunction "K3_16") (pintype "bidirectional"))
    )
    (net (code "69") (name "Net-(IC2-COM3{slash}KS2)") (class "Default")
      (node (ref "IC2") (pin "5") (pinfunction "COM3/KS2_5") (pintype "output"))
      (node (ref "LED5") (pin "13") (pinfunction "K4_13") (pintype "bidirectional"))
    )
    (net (code "70") (name "Net-(IC2-COM4)") (class "Default")
      (node (ref "IC2") (pin "6") (pinfunction "COM4_6") (pintype "output"))
      (node (ref "LED5") (pin "3") (pinfunction "K5_3") (pintype "bidirectional"))
    )
    (net (code "71") (name "Net-(IC2-COM5)") (class "Default")
      (node (ref "IC2") (pin "7") (pinfunction "COM5_7") (pintype "output"))
      (node (ref "LED5") (pin "6") (pinfunction "K6_6") (pintype "bidirectional"))
    )
    (net (code "72") (name "Net-(IC2-COM6)") (class "Default")
      (node (ref "IC2") (pin "8") (pinfunction "COM6_8") (pintype "output"))
      (node (ref "LED5") (pin "9") (pinfunction "K7_9") (pintype "bidirectional"))
    )
    (net (code "73") (name "Net-(IC2-COM7)") (class "Default")
      (node (ref "IC2") (pin "9") (pinfunction "COM7_9") (pintype "output"))
      (node (ref "LED5") (pin "12") (pinfunction "K8_12") (pintype "bidirectional"))
    )
    (net (code "74") (name "Net-(IC2-ROW0{slash}A2)") (class "Default")
      (node (ref "IC2") (pin "25") (pinfunction "ROW0/A2_25") (pintype "bidirectional"))
      (node (ref "LED5") (pin "24") (pinfunction "A1_24") (pintype "bidirectional"))
    )
    (net (code "75") (name "Net-(IC2-ROW1{slash}A1)") (class "Default")
      (node (ref "IC2") (pin "24") (pinfunction "ROW1/A1_24") (pintype "bidirectional"))
      (node (ref "LED5") (pin "21") (pinfunction "A3_21") (pintype "bidirectional"))
      (node (ref "R10") (pin "2") (pinfunction "2_2") (pintype "passive"))
    )
    (net (code "76") (name "Net-(IC2-ROW2{slash}A0)") (class "Default")
      (node (ref "IC2") (pin "23") (pinfunction "ROW2/A0_23") (pintype "bidirectional"))
      (node (ref "LED5") (pin "18") (pinfunction "A5_18") (pintype "bidirectional"))
    )
    (net (code "77") (name "Net-(IC2-ROW3{slash}K1)") (class "Default")
      (node (ref "IC2") (pin "22") (pinfunction "ROW3/K1_22") (pintype "bidirectional"))
      (node (ref "LED5") (pin "15") (pinfunction "A7_15") (pintype "bidirectional"))
    )
    (net (code "78") (name "Net-(IC2-ROW4{slash}K2)") (class "Default")
      (node (ref "IC2") (pin "21") (pinfunction "ROW4/K2_21") (pintype "bidirectional"))
      (node (ref "LED5") (pin "1") (pinfunction "A9_1") (pintype "bidirectional"))
    )
    (net (code "79") (name "Net-(IC2-ROW5{slash}K3)") (class "Default")
      (node (ref "IC2") (pin "20") (pinfunction "ROW5/K3_20") (pintype "bidirectional"))
      (node (ref "LED5") (pin "4") (pinfunction "A11_4") (pintype "bidirectional"))
    )
    (net (code "80") (name "Net-(IC2-ROW6{slash}K4)") (class "Default")
      (node (ref "IC2") (pin "19") (pinfunction "ROW6/K4_19") (pintype "bidirectional"))
      (node (ref "LED5") (pin "7") (pinfunction "A13_7") (pintype "bidirectional"))
    )
    (net (code "81") (name "Net-(IC2-ROW7{slash}K5)") (class "Default")
      (node (ref "IC2") (pin "18") (pinfunction "ROW7/K5_18") (pintype "bidirectional"))
      (node (ref "LED5") (pin "10") (pinfunction "A15_10") (pintype "bidirectional"))
    )
    (net (code "82") (name "Net-(IC2-ROW8{slash}K6)") (class "Default")
      (node (ref "IC2") (pin "17") (pinfunction "ROW8/K6_17") (pintype "bidirectional"))
      (node (ref "LED5") (pin "23") (pinfunction "A2_23") (pintype "bidirectional"))
    )
    (net (code "83") (name "Net-(IC2-ROW9{slash}K7)") (class "Default")
      (node (ref "IC2") (pin "16") (pinfunction "ROW9/K7_16") (pintype "bidirectional"))
      (node (ref "LED5") (pin "20") (pinfunction "A4_20") (pintype "bidirectional"))
    )
    (net (code "84") (name "Net-(IC2-ROW10{slash}K8)") (class "Default")
      (node (ref "IC2") (pin "15") (pinfunction "ROW10/K8_15") (pintype "bidirectional"))
      (node (ref "LED5") (pin "17") (pinfunction "A6_17") (pintype "bidirectional"))
    )
    (net (code "85") (name "Net-(IC2-ROW11{slash}K9)") (class "Default")
      (node (ref "IC2") (pin "14") (pinfunction "ROW11/K9_14") (pintype "bidirectional"))
      (node (ref "LED5") (pin "14") (pinfunction "A8_14") (pintype "bidirectional"))
    )
    (net (code "86") (name "Net-(IC2-ROW12{slash}K10)") (class "Default")
      (node (ref "IC2") (pin "13") (pinfunction "ROW12/K10_13") (pintype "bidirectional"))
      (node (ref "LED5") (pin "2") (pinfunction "A10_2") (pintype "bidirectional"))
    )
    (net (code "87") (name "Net-(IC2-ROW13{slash}K11)") (class "Default")
      (node (ref "IC2") (pin "12") (pinfunction "ROW13/K11_12") (pintype "bidirectional"))
      (node (ref "LED5") (pin "5") (pinfunction "A12_5") (pintype "bidirectional"))
    )
    (net (code "88") (name "Net-(IC2-ROW14{slash}K12)") (class "Default")
      (node (ref "IC2") (pin "11") (pinfunction "ROW14/K12_11") (pintype "bidirectional"))
      (node (ref "LED5") (pin "8") (pinfunction "A14_8") (pintype "bidirectional"))
    )
    (net (code "89") (name "Net-(IC2-ROW15{slash}K13{slash}INT)") (class "Default")
      (node (ref "IC2") (pin "10") (pinfunction "ROW15/K13/INT_10") (pintype "bidirectional"))
      (node (ref "LED5") (pin "11") (pinfunction "A16_11") (pintype "bidirectional"))
    )
    (net (code "90") (name "Net-(IC3-COM0{slash}AD)") (class "Default")
      (node (ref "D3") (pin "A") (pinfunction "A_A") (pintype "passive"))
      (node (ref "IC3") (pin "2") (pinfunction "COM0/AD_2") (pintype "output"))
      (node (ref "LED6") (pin "22") (pinfunction "K1_22") (pintype "bidirectional"))
    )
    (net (code "91") (name "Net-(IC3-COM1{slash}KS0)") (class "Default")
      (node (ref "IC3") (pin "3") (pinfunction "COM1/KS0_3") (pintype "output"))
      (node (ref "LED6") (pin "19") (pinfunction "K2_19") (pintype "bidirectional"))
    )
    (net (code "92") (name "Net-(IC3-COM2{slash}KS1)") (class "Default")
      (node (ref "IC3") (pin "4") (pinfunction "COM2/KS1_4") (pintype "output"))
      (node (ref "LED6") (pin "16") (pinfunction "K3_16") (pintype "bidirectional"))
    )
    (net (code "93") (name "Net-(IC3-COM3{slash}KS2)") (class "Default")
      (node (ref "IC3") (pin "5") (pinfunction "COM3/KS2_5") (pintype "output"))
      (node (ref "LED6") (pin "13") (pinfunction "K4_13") (pintype "bidirectional"))
    )
    (net (code "94") (name "Net-(IC3-COM4)") (class "Default")
      (node (ref "IC3") (pin "6") (pinfunction "COM4_6") (pintype "output"))
      (node (ref "LED6") (pin "3") (pinfunction "K5_3") (pintype "bidirectional"))
    )
    (net (code "95") (name "Net-(IC3-COM5)") (class "Default")
      (node (ref "IC3") (pin "7") (pinfunction "COM5_7") (pintype "output"))
      (node (ref "LED6") (pin "6") (pinfunction "K6_6") (pintype "bidirectional"))
    )
    (net (code "96") (name "Net-(IC3-COM6)") (class "Default")
      (node (ref "IC3") (pin "8") (pinfunction "COM6_8") (pintype "output"))
      (node (ref "LED6") (pin "9") (pinfunction "K7_9") (pintype "bidirectional"))
    )
    (net (code "97") (name "Net-(IC3-COM7)") (class "Default")
      (node (ref "IC3") (pin "9") (pinfunction "COM7_9") (pintype "output"))
      (node (ref "LED6") (pin "12") (pinfunction "K8_12") (pintype "bidirectional"))
    )
    (net (code "98") (name "Net-(IC3-ROW0{slash}A2)") (class "Default")
      (node (ref "IC3") (pin "25") (pinfunction "ROW0/A2_25") (pintype "bidirectional"))
      (node (ref "LED6") (pin "24") (pinfunction "A1_24") (pintype "bidirectional"))
    )
    (net (code "99") (name "Net-(IC3-ROW1{slash}A1)") (class "Default")
      (node (ref "IC3") (pin "24") (pinfunction "ROW1/A1_24") (pintype "bidirectional"))
      (node (ref "LED6") (pin "21") (pinfunction "A3_21") (pintype "bidirectional"))
    )
    (net (code "100") (name "Net-(IC3-ROW2{slash}A0)") (class "Default")
      (node (ref "IC3") (pin "23") (pinfunction "ROW2/A0_23") (pintype "bidirectional"))
      (node (ref "LED6") (pin "18") (pinfunction "A5_18") (pintype "bidirectional"))
      (node (ref "R26") (pin "2") (pinfunction "2_2") (pintype "passive"))
    )
    (net (code "101") (name "Net-(IC3-ROW3{slash}K1)") (class "Default")
      (node (ref "IC3") (pin "22") (pinfunction "ROW3/K1_22") (pintype "bidirectional"))
      (node (ref "LED6") (pin "15") (pinfunction "A7_15") (pintype "bidirectional"))
    )
    (net (code "102") (name "Net-(IC3-ROW4{slash}K2)") (class "Default")
      (node (ref "IC3") (pin "21") (pinfunction "ROW4/K2_21") (pintype "bidirectional"))
      (node (ref "LED6") (pin "1") (pinfunction "A9_1") (pintype "bidirectional"))
    )
    (net (code "103") (name "Net-(IC3-ROW5{slash}K3)") (class "Default")
      (node (ref "IC3") (pin "20") (pinfunction "ROW5/K3_20") (pintype "bidirectional"))
      (node (ref "LED6") (pin "4") (pinfunction "A11_4") (pintype "bidirectional"))
    )
    (net (code "104") (name "Net-(IC3-ROW6{slash}K4)") (class "Default")
      (node (ref "IC3") (pin "19") (pinfunction "ROW6/K4_19") (pintype "bidirectional"))
      (node (ref "LED6") (pin "7") (pinfunction "A13_7") (pintype "bidirectional"))
    )
    (net (code "105") (name "Net-(IC3-ROW7{slash}K5)") (class "Default")
      (node (ref "IC3") (pin "18") (pinfunction "ROW7/K5_18") (pintype "bidirectional"))
      (node (ref "LED6") (pin "10") (pinfunction "A15_10") (pintype "bidirectional"))
    )
    (net (code "106") (name "Net-(IC3-ROW8{slash}K6)") (class "Default")
      (node (ref "IC3") (pin "17") (pinfunction "ROW8/K6_17") (pintype "bidirectional"))
      (node (ref "LED6") (pin "23") (pinfunction "A2_23") (pintype "bidirectional"))
    )
    (net (code "107") (name "Net-(IC3-ROW9{slash}K7)") (class "Default")
      (node (ref "IC3") (pin "16") (pinfunction "ROW9/K7_16") (pintype "bidirectional"))
      (node (ref "LED6") (pin "20") (pinfunction "A4_20") (pintype "bidirectional"))
    )
    (net (code "108") (name "Net-(IC3-ROW10{slash}K8)") (class "Default")
      (node (ref "IC3") (pin "15") (pinfunction "ROW10/K8_15") (pintype "bidirectional"))
      (node (ref "LED6") (pin "17") (pinfunction "A6_17") (pintype "bidirectional"))
    )
    (net (code "109") (name "Net-(IC3-ROW11{slash}K9)") (class "Default")
      (node (ref "IC3") (pin "14") (pinfunction "ROW11/K9_14") (pintype "bidirectional"))
      (node (ref "LED6") (pin "14") (pinfunction "A8_14") (pintype "bidirectional"))
    )
    (net (code "110") (name "Net-(IC3-ROW12{slash}K10)") (class "Default")
      (node (ref "IC3") (pin "13") (pinfunction "ROW12/K10_13") (pintype "bidirectional"))
      (node (ref "LED6") (pin "2") (pinfunction "A10_2") (pintype "bidirectional"))
    )
    (net (code "111") (name "Net-(IC3-ROW13{slash}K11)") (class "Default")
      (node (ref "IC3") (pin "12") (pinfunction "ROW13/K11_12") (pintype "bidirectional"))
      (node (ref "LED6") (pin "5") (pinfunction "A12_5") (pintype "bidirectional"))
    )
    (net (code "112") (name "Net-(IC3-ROW14{slash}K12)") (class "Default")
      (node (ref "IC3") (pin "11") (pinfunction "ROW14/K12_11") (pintype "bidirectional"))
      (node (ref "LED6") (pin "8") (pinfunction "A14_8") (pintype "bidirectional"))
    )
    (net (code "113") (name "Net-(IC3-ROW15{slash}K13{slash}INT)") (class "Default")
      (node (ref "IC3") (pin "10") (pinfunction "ROW15/K13/INT_10") (pintype "bidirectional"))
      (node (ref "LED6") (pin "11") (pinfunction "A16_11") (pintype "bidirectional"))
    )
    (net (code "114") (name "Net-(IC4-COM0{slash}AD)") (class "Default")
      (node (ref "D4") (pin "A") (pinfunction "A_A") (pintype "passive"))
      (node (ref "IC4") (pin "2") (pinfunction "COM0/AD_2") (pintype "output"))
      (node (ref "LED7") (pin "22") (pinfunction "K1_22") (pintype "bidirectional"))
    )
    (net (code "115") (name "Net-(IC4-COM1{slash}KS0)") (class "Default")
      (node (ref "IC4") (pin "3") (pinfunction "COM1/KS0_3") (pintype "output"))
      (node (ref "LED7") (pin "19") (pinfunction "K2_19") (pintype "bidirectional"))
    )
    (net (code "116") (name "Net-(IC4-COM2{slash}KS1)") (class "Default")
      (node (ref "IC4") (pin "4") (pinfunction "COM2/KS1_4") (pintype "output"))
      (node (ref "LED7") (pin "16") (pinfunction "K3_16") (pintype "bidirectional"))
    )
    (net (code "117") (name "Net-(IC4-COM3{slash}KS2)") (class "Default")
      (node (ref "IC4") (pin "5") (pinfunction "COM3/KS2_5") (pintype "output"))
      (node (ref "LED7") (pin "13") (pinfunction "K4_13") (pintype "bidirectional"))
    )
    (net (code "118") (name "Net-(IC4-COM4)") (class "Default")
      (node (ref "IC4") (pin "6") (pinfunction "COM4_6") (pintype "output"))
      (node (ref "LED7") (pin "3") (pinfunction "K5_3") (pintype "bidirectional"))
    )
    (net (code "119") (name "Net-(IC4-COM5)") (class "Default")
      (node (ref "IC4") (pin "7") (pinfunction "COM5_7") (pintype "output"))
      (node (ref "LED7") (pin "6") (pinfunction "K6_6") (pintype "bidirectional"))
    )
    (net (code "120") (name "Net-(IC4-COM6)") (class "Default")
      (node (ref "IC4") (pin "8") (pinfunction "COM6_8") (pintype "output"))
      (node (ref "LED7") (pin "9") (pinfunction "K7_9") (pintype "bidirectional"))
    )
    (net (code "121") (name "Net-(IC4-COM7)") (class "Default")
      (node (ref "IC4") (pin "9") (pinfunction "COM7_9") (pintype "output"))
      (node (ref "LED7") (pin "12") (pinfunction "K8_12") (pintype "bidirectional"))
    )
    (net (code "122") (name "Net-(IC4-ROW0{slash}A2)") (class "Default")
      (node (ref "IC4") (pin "25") (pinfunction "ROW0/A2_25") (pintype "bidirectional"))
      (node (ref "LED7") (pin "24") (pinfunction "A1_24") (pintype "bidirectional"))
      (node (ref "R29") (pin "2") (pinfunction "2_2") (pintype "passive"))
    )
    (net (code "123") (name "Net-(IC4-ROW1{slash}A1)") (class "Default")
      (node (ref "IC4") (pin "24") (pinfunction "ROW1/A1_24") (pintype "bidirectional"))
      (node (ref "LED7") (pin "21") (pinfunction "A3_21") (pintype "bidirectional"))
      (node (ref "R30") (pin "2") (pinfunction "2_2") (pintype "passive"))
    )
    (net (code "124") (name "Net-(IC4-ROW2{slash}A0)") (class "Default")
      (node (ref "IC4") (pin "23") (pinfunction "ROW2/A0_23") (pintype "bidirectional"))
      (node (ref "LED7") (pin "18") (pinfunction "A5_18") (pintype "bidirectional"))
    )
    (net (code "125") (name "Net-(IC4-ROW3{slash}K1)") (class "Default")
      (node (ref "IC4") (pin "22") (pinfunction "ROW3/K1_22") (pintype "bidirectional"))
      (node (ref "LED7") (pin "15") (pinfunction "A7_15") (pintype "bidirectional"))
    )
    (net (code "126") (name "Net-(IC4-ROW4{slash}K2)") (class "Default")
      (node (ref "IC4") (pin "21") (pinfunction "ROW4/K2_21") (pintype "bidirectional"))
      (node (ref "LED7") (pin "1") (pinfunction "A9_1") (pintype "bidirectional"))
    )
    (net (code "127") (name "Net-(IC4-ROW5{slash}K3)") (class "Default")
      (node (ref "IC4") (pin "20") (pinfunction "ROW5/K3_20") (pintype "bidirectional"))
      (node (ref "LED7") (pin "4") (pinfunction "A11_4") (pintype "bidirectional"))
    )
    (net (code "128") (name "Net-(IC4-ROW6{slash}K4)") (class "Default")
      (node (ref "IC4") (pin "19") (pinfunction "ROW6/K4_19") (pintype "bidirectional"))
      (node (ref "LED7") (pin "7") (pinfunction "A13_7") (pintype "bidirectional"))
    )
    (net (code "129") (name "Net-(IC4-ROW7{slash}K5)") (class "Default")
      (node (ref "IC4") (pin "18") (pinfunction "ROW7/K5_18") (pintype "bidirectional"))
      (node (ref "LED7") (pin "10") (pinfunction "A15_10") (pintype "bidirectional"))
    )
    (net (code "130") (name "Net-(IC4-ROW8{slash}K6)") (class "Default")
      (node (ref "IC4") (pin "17") (pinfunction "ROW8/K6_17") (pintype "bidirectional"))
      (node (ref "LED7") (pin "23") (pinfunction "A2_23") (pintype "bidirectional"))
    )
    (net (code "131") (name "Net-(IC4-ROW9{slash}K7)") (class "Default")
      (node (ref "IC4") (pin "16") (pinfunction "ROW9/K7_16") (pintype "bidirectional"))
      (node (ref "LED7") (pin "20") (pinfunction "A4_20") (pintype "bidirectional"))
    )
    (net (code "132") (name "Net-(IC4-ROW10{slash}K8)") (class "Default")
      (node (ref "IC4") (pin "15") (pinfunction "ROW10/K8_15") (pintype "bidirectional"))
      (node (ref "LED7") (pin "17") (pinfunction "A6_17") (pintype "bidirectional"))
    )
    (net (code "133") (name "Net-(IC4-ROW11{slash}K9)") (class "Default")
      (node (ref "IC4") (pin "14") (pinfunction "ROW11/K9_14") (pintype "bidirectional"))
      (node (ref "LED7") (pin "14") (pinfunction "A8_14") (pintype "bidirectional"))
    )
    (net (code "134") (name "Net-(IC4-ROW12{slash}K10)") (class "Default")
      (node (ref "IC4") (pin "13") (pinfunction "ROW12/K10_13") (pintype "bidirectional"))
      (node (ref "LED7") (pin "2") (pinfunction "A10_2") (pintype "bidirectional"))
    )
    (net (code "135") (name "Net-(IC4-ROW13{slash}K11)") (class "Default")
      (node (ref "IC4") (pin "12") (pinfunction "ROW13/K11_12") (pintype "bidirectional"))
      (node (ref "LED7") (pin "5") (pinfunction "A12_5") (pintype "bidirectional"))
    )
    (net (code "136") (name "Net-(IC4-ROW14{slash}K12)") (class "Default")
      (node (ref "IC4") (pin "11") (pinfunction "ROW14/K12_11") (pintype "bidirectional"))
      (node (ref "LED7") (pin "8") (pinfunction "A14_8") (pintype "bidirectional"))
    )
    (net (code "137") (name "Net-(IC4-ROW15{slash}K13{slash}INT)") (class "Default")
      (node (ref "IC4") (pin "10") (pinfunction "ROW15/K13/INT_10") (pintype "bidirectional"))
      (node (ref "LED7") (pin "11") (pinfunction "A16_11") (pintype "bidirectional"))
    )
    (net (code "138") (name "Net-(LED1-PadC)") (class "Default")
      (node (ref "LED1") (pin "C") (pinfunction "C_C") (pintype "passive"))
      (node (ref "R1") (pin "1") (pinfunction "1_1") (pintype "passive"))
    )
    (net (code "139") (name "Net-(LED2-PadC)") (class "Default")
      (node (ref "LED2") (pin "C") (pinfunction "C_C") (pintype "passive"))
      (node (ref "R2") (pin "1") (pinfunction "1_1") (pintype "passive"))
    )
    (net (code "140") (name "Net-(PWR-PadC)") (class "Default")
      (node (ref "PWR") (pin "C") (pinfunction "C_C") (pintype "passive"))
      (node (ref "R11") (pin "2") (pinfunction "2_2") (pintype "passive"))
    )
    (net (code "141") (name "Net-(R4-Pad1)") (class "Default")
      (node (ref "R4") (pin "1") (pinfunction "1_1") (pintype "passive"))
      (node (ref "S1") (pin "1") (pinfunction "1_1") (pintype "passive"))
    )
    (net (code "142") (name "unconnected-(IC5-COM4-Pad6)") (class "Default")
      (node (ref "IC5") (pin "6") (pinfunction "COM4_6") (pintype "output"))
    )
    (net (code "143") (name "unconnected-(IC5-COM5-Pad7)") (class "Default")
      (node (ref "IC5") (pin "7") (pinfunction "COM5_7") (pintype "output"))
    )
    (net (code "144") (name "unconnected-(IC5-COM6-Pad8)") (class "Default")
      (node (ref "IC5") (pin "8") (pinfunction "COM6_8") (pintype "output"))
    )
    (net (code "145") (name "unconnected-(IC5-COM7-Pad9)") (class "Default")
      (node (ref "IC5") (pin "9") (pinfunction "COM7_9") (pintype "output"))
    )
    (net (code "146") (name "unconnected-(IC5-ROW8{slash}K6-Pad17)") (class "Default")
      (node (ref "IC5") (pin "17") (pinfunction "ROW8/K6_17") (pintype "bidirectional"))
    )
    (net (code "147") (name "unconnected-(IC5-ROW9{slash}K7-Pad16)") (class "Default")
      (node (ref "IC5") (pin "16") (pinfunction "ROW9/K7_16") (pintype "bidirectional"))
    )
    (net (code "148") (name "unconnected-(IC5-ROW10{slash}K8-Pad15)") (class "Default")
      (node (ref "IC5") (pin "15") (pinfunction "ROW10/K8_15") (pintype "bidirectional"))
    )
    (net (code "149") (name "unconnected-(IC5-ROW11{slash}K9-Pad14)") (class "Default")
      (node (ref "IC5") (pin "14") (pinfunction "ROW11/K9_14") (pintype "bidirectional"))
    )
    (net (code "150") (name "unconnected-(IC5-ROW12{slash}K10-Pad13)") (class "Default")
      (node (ref "IC5") (pin "13") (pinfunction "ROW12/K10_13") (pintype "bidirectional"))
    )
    (net (code "151") (name "unconnected-(IC5-ROW13{slash}K11-Pad12)") (class "Default")
      (node (ref "IC5") (pin "12") (pinfunction "ROW13/K11_12") (pintype "bidirectional"))
    )
    (net (code "152") (name "unconnected-(IC5-ROW14{slash}K12-Pad11)") (class "Default")
      (node (ref "IC5") (pin "11") (pinfunction "ROW14/K12_11") (pintype "bidirectional"))
    )
    (net (code "153") (name "unconnected-(IC5-ROW15{slash}K13{slash}INT-Pad10)") (class "Default")
      (node (ref "IC5") (pin "10") (pinfunction "ROW15/K13/INT_10") (pintype "bidirectional"))
    )
    (net (code "154") (name "unconnected-(U1-NC-Pad34)") (class "Default")
      (node (ref "U1") (pin "34") (pinfunction "NC_34") (pintype "no_connect"))
    )
    (net (code "155") (name "unconnected-(U1-NC_2-Pad12)") (class "Default")
      (node (ref "U1") (pin "12") (pinfunction "NC_2_12") (pintype "no_connect"))
    )
    (net (code "156") (name "unconnected-(U1-NC_3-Pad13)") (class "Default")
      (node (ref "U1") (pin "13") (pinfunction "NC_3_13") (pintype "no_connect"))
    )
    (net (code "157") (name "unconnected-(U1-NC_4-Pad33)") (class "Default")
      (node (ref "U1") (pin "33") (pinfunction "NC_4_33") (pintype "no_connect"))
    )
    (net (code "158") (name "unconnected-(U1-OSC1{slash}CLKI{slash}RA7-Pad30)") (class "Default")
      (node (ref "U1") (pin "30") (pinfunction "OSC1/CLKI/RA7_30") (pintype "bidirectional"))
    )
    (net (code "159") (name "unconnected-(U1-OSC2{slash}CLKO{slash}RA6-Pad31)") (class "Default")
      (node (ref "U1") (pin "31") (pinfunction "OSC2/CLKO/RA6_31") (pintype "bidirectional"))
    )
    (net (code "160") (name "unconnected-(U1-RA0{slash}AN0-Pad19)") (class "Default")
      (node (ref "U1") (pin "19") (pinfunction "RA0/AN0_19") (pintype "bidirectional"))
    )
    (net (code "161") (name "unconnected-(U1-RA1{slash}AN1-Pad20)") (class "Default")
      (node (ref "U1") (pin "20") (pinfunction "RA1/AN1_20") (pintype "bidirectional"))
    )
    (net (code "162") (name "unconnected-(U1-RA2{slash}AN2{slash}VREF-{slash}CVREF-Pad21)") (class "Default")
      (node (ref "U1") (pin "21") (pinfunction "RA2/AN2/VREF-/CVREF_21") (pintype "bidirectional"))
    )
    (net (code "163") (name "unconnected-(U1-RA3{slash}AN3{slash}VREF+-Pad22)") (class "Default")
      (node (ref "U1") (pin "22") (pinfunction "RA3/AN3/VREF+_22") (pintype "bidirectional"))
    )
    (net (code "164") (name "unconnected-(U1-RA4{slash}T0CKI{slash}C1OUT-Pad23)") (class "Default")
      (node (ref "U1") (pin "23") (pinfunction "RA4/T0CKI/C1OUT_23") (pintype "bidirectional"))
    )
    (net (code "165") (name "unconnected-(U1-RA5{slash}AN4{slash}~{SS{slash}HLVDIN{slash}C2OUT}-Pad24)") (class "Default")
      (node (ref "U1") (pin "24") (pinfunction "RA5/AN4/~{SS/HLVDIN/C2OUT}_24") (pintype "bidirectional"))
    )
    (net (code "166") (name "unconnected-(U1-RC0{slash}T1OSO{slash}T13CKI-Pad32)") (class "Default")
      (node (ref "U1") (pin "32") (pinfunction "RC0/T1OSO/T13CKI_32") (pintype "bidirectional"))
    )
    (net (code "167") (name "unconnected-(U1-RC1{slash}T1OSI{slash}CCP2-Pad35)") (class "Default")
      (node (ref "U1") (pin "35") (pinfunction "RC1/T1OSI/CCP2_35") (pintype "bidirectional"))
    )
    (net (code "168") (name "unconnected-(U1-RC2{slash}CCP1{slash}P1A-Pad36)") (class "Default")
      (node (ref "U1") (pin "36") (pinfunction "RC2/CCP1/P1A_36") (pintype "bidirectional"))
    )
    (net (code "169") (name "unconnected-(U1-RC5{slash}SDO-Pad43)") (class "Default")
      (node (ref "U1") (pin "43") (pinfunction "RC5/SDO_43") (pintype "bidirectional"))
    )
    (net (code "170") (name "unconnected-(U1-RC6{slash}TX{slash}CK-Pad44)") (class "Default")
      (node (ref "U1") (pin "44") (pinfunction "RC6/TX/CK_44") (pintype "bidirectional"))
    )
    (net (code "171") (name "unconnected-(U1-RC7{slash}RX{slash}DT-Pad1)") (class "Default")
      (node (ref "U1") (pin "1") (pinfunction "RC7/RX/DT_1") (pintype "bidirectional"))
    )
    (net (code "172") (name "unconnected-(U1-RD0{slash}PSP0-Pad38)") (class "Default")
      (node (ref "U1") (pin "38") (pinfunction "RD0/PSP0_38") (pintype "bidirectional"))
    )
    (net (code "173") (name "unconnected-(U1-RD1{slash}PSP1-Pad39)") (class "Default")
      (node (ref "U1") (pin "39") (pinfunction "RD1/PSP1_39") (pintype "bidirectional"))
    )
    (net (code "174") (name "unconnected-(U1-RD2{slash}PSP2-Pad40)") (class "Default")
      (node (ref "U1") (pin "40") (pinfunction "RD2/PSP2_40") (pintype "bidirectional"))
    )
    (net (code "175") (name "unconnected-(U1-RD3{slash}PSP3-Pad41)") (class "Default")
      (node (ref "U1") (pin "41") (pinfunction "RD3/PSP3_41") (pintype "bidirectional"))
    )
    (net (code "176") (name "unconnected-(U1-RD4{slash}PSP4-Pad2)") (class "Default")
      (node (ref "U1") (pin "2") (pinfunction "RD4/PSP4_2") (pintype "bidirectional"))
    )
    (net (code "177") (name "unconnected-(U1-RD5{slash}PSP5{slash}P1B-Pad3)") (class "Default")
      (node (ref "U1") (pin "3") (pinfunction "RD5/PSP5/P1B_3") (pintype "bidirectional"))
    )
    (net (code "178") (name "unconnected-(U1-RE0{slash}~{RD{slash}AN5}-Pad25)") (class "Default")
      (node (ref "U1") (pin "25") (pinfunction "RE0/~{RD/AN5}_25") (pintype "bidirectional"))
    )
    (net (code "179") (name "unconnected-(U1-RE1{slash}~{WR{slash}AN6}-Pad26)") (class "Default")
      (node (ref "U1") (pin "26") (pinfunction "RE1/~{WR/AN6}_26") (pintype "bidirectional"))
    )
    (net (code "180") (name "unconnected-(U1-RE2{slash}~{CS{slash}AN7}-Pad27)") (class "Default")
      (node (ref "U1") (pin "27") (pinfunction "RE2/~{CS/AN7}_27") (pintype "bidirectional"))
    )
    (net (code "181") (name "unconnected-(U2-6Y-Pad12)") (class "Default")
      (node (ref "U2") (pin "12") (pinfunction "6Y_12") (pintype "output"))
    )
    (net (code "182") (name "unconnected-(USB-D+-Pad3)") (class "Default")
      (node (ref "USB") (pin "3") (pinfunction "D+_3") (pintype "bidirectional"))
    )
    (net (code "183") (name "unconnected-(USB-D--Pad2)") (class "Default")
      (node (ref "USB") (pin "2") (pinfunction "D-_2") (pintype "bidirectional"))
    )
    (net (code "184") (name "unconnected-(USB-ID-Pad4)") (class "Default")
      (node (ref "USB") (pin "4") (pinfunction "ID_4") (pintype "bidirectional"))
    )
  )
)
